# V1.net
KiCad netlist of a schematic drawn in EAGLE
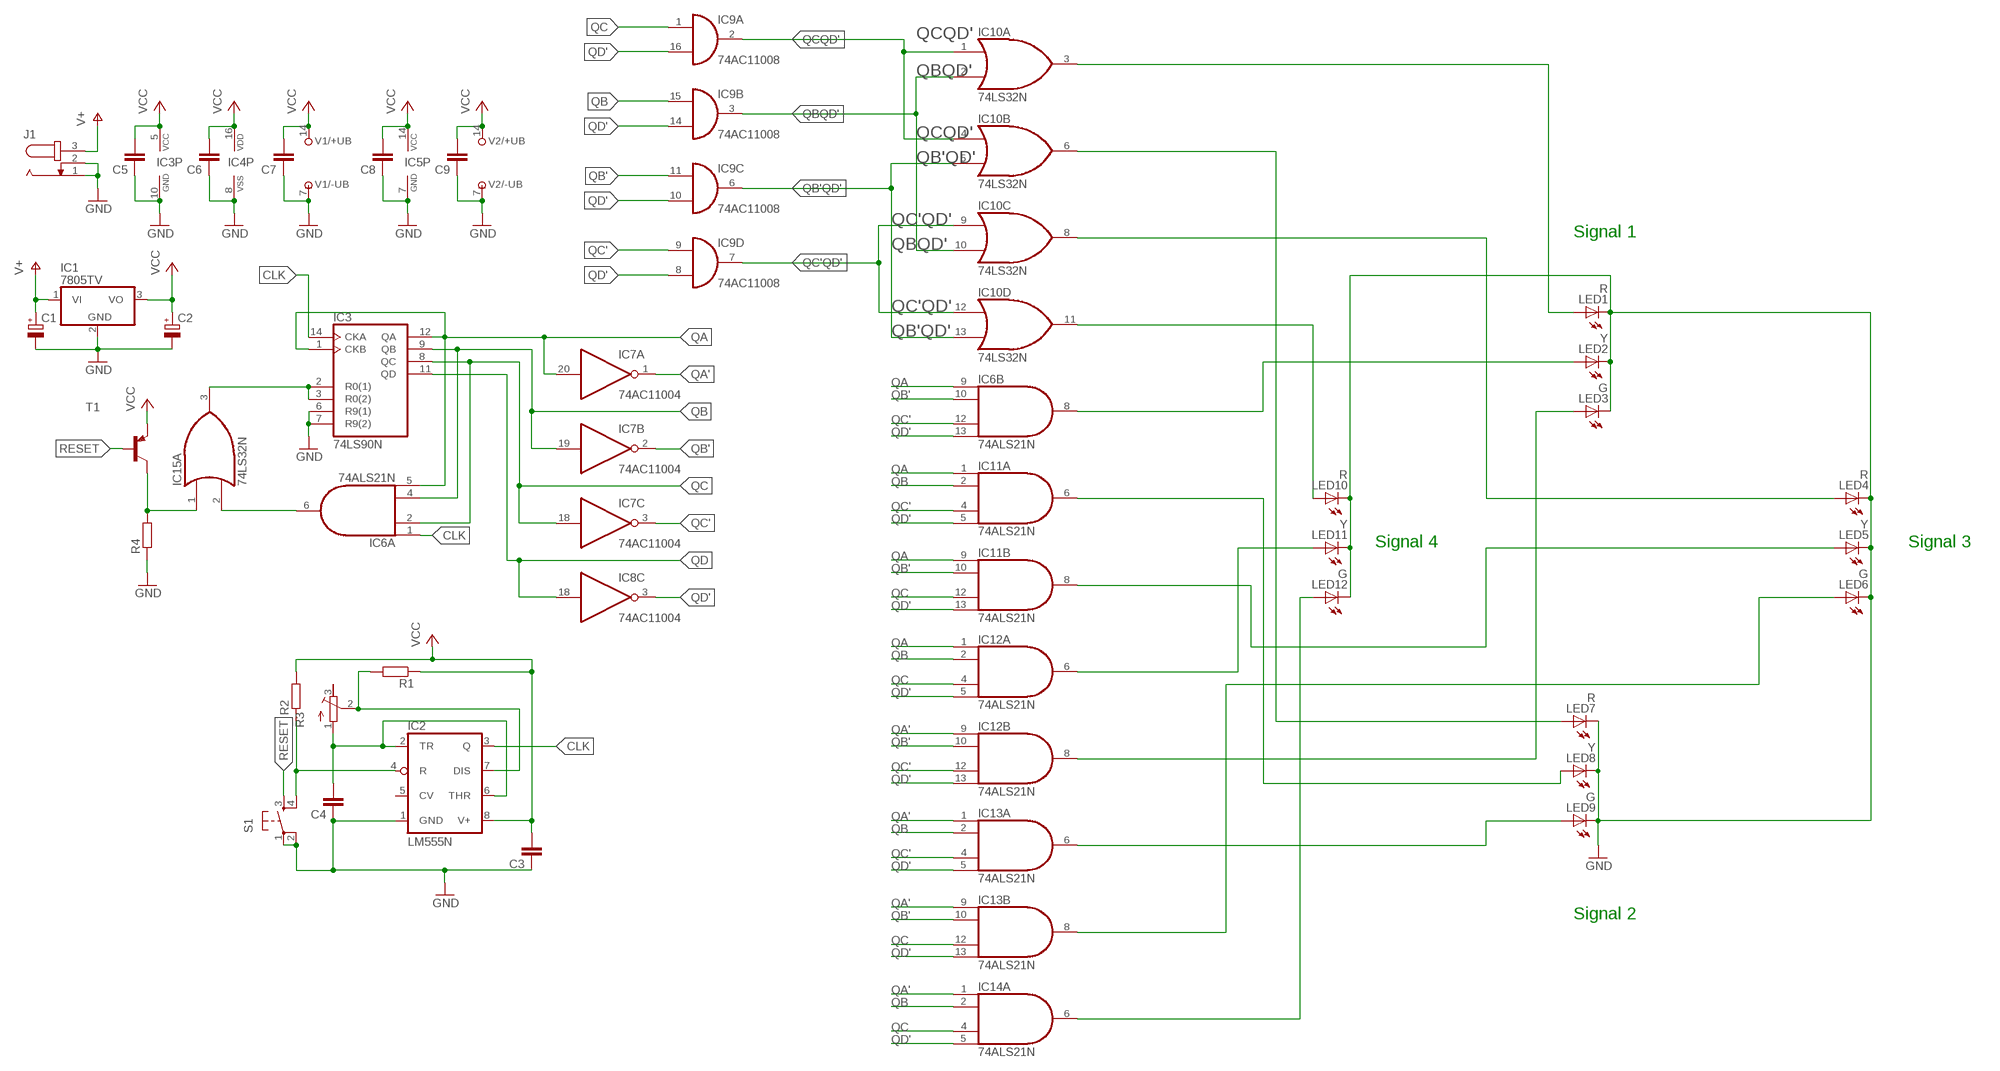
[diagram p0: schematic, sheet 1]

(export (version "E")
  (design (tool "Eeschema 10.0.6"))
  (components
    (comp (ref "C1")
      (value "CPOL-EUE3.5-8")
      (footprint "eagle-import:E3,5-8")
      (libsource (lib "eagle-import") (part "CPOL-EUE3.5-8"))
    )
    (comp (ref "C2")
      (value "CPOL-EUE3.5-8")
      (footprint "eagle-import:E3,5-8")
      (libsource (lib "eagle-import") (part "CPOL-EUE3.5-8"))
    )
    (comp (ref "C3")
      (value "C-EU050-035X075")
      (footprint "eagle-import:C050-035X075")
      (libsource (lib "eagle-import") (part "C-EU050-035X075"))
    )
    (comp (ref "C4")
      (value "C-EU050-035X075")
      (footprint "eagle-import:C050-035X075")
      (libsource (lib "eagle-import") (part "C-EU050-035X075"))
    )
    (comp (ref "C5")
      (value "C-EU050-035X075")
      (footprint "eagle-import:C050-035X075")
      (libsource (lib "eagle-import") (part "C-EU050-035X075"))
    )
    (comp (ref "C6")
      (value "C-EU050-035X075")
      (footprint "eagle-import:C050-035X075")
      (libsource (lib "eagle-import") (part "C-EU050-035X075"))
    )
    (comp (ref "C7")
      (value "C-EU050-035X075")
      (footprint "eagle-import:C050-035X075")
      (libsource (lib "eagle-import") (part "C-EU050-035X075"))
    )
    (comp (ref "C8")
      (value "C-EU050-035X075")
      (footprint "eagle-import:C050-035X075")
      (libsource (lib "eagle-import") (part "C-EU050-035X075"))
    )
    (comp (ref "C9")
      (value "C-EU050-035X075")
      (footprint "eagle-import:C050-035X075")
      (libsource (lib "eagle-import") (part "C-EU050-035X075"))
    )
    (comp (ref "IC1")
      (value "7805TV")
      (footprint "eagle-import:TO220V")
      (libsource (lib "eagle-import") (part "78TV05"))
    )
    (comp (ref "IC2")
      (value "LM555N")
      (footprint "eagle-import:DIL08")
      (libsource (lib "eagle-import") (part "555NLM"))
    )
    (comp (ref "IC3")
      (value "74LS90N")
      (footprint "eagle-import:DIL14")
      (libsource (lib "eagle-import") (part "7490NLS"))
    )
    (comp (ref "IC4")
      (value "4028N")
      (footprint "eagle-import:DIL16")
      (libsource (lib "eagle-import") (part "4028N"))
    )
    (comp (ref "IC5")
      (value "74AC04N")
      (footprint "eagle-import:DIL14")
      (libsource (lib "eagle-import") (part "7404NAC"))
    )
    (comp (ref "IC6")
      (value "74ALS21N")
      (footprint "eagle-import:DIL14")
      (libsource (lib "eagle-import") (part "7421NALS"))
    )
    (comp (ref "IC7")
      (value "74AC11004")
      (footprint "eagle-import:DIL20")
      (libsource (lib "eagle-import") (part "74AC11004"))
    )
    (comp (ref "IC8")
      (value "74AC11004")
      (footprint "eagle-import:DIL20")
      (libsource (lib "eagle-import") (part "74AC11004"))
    )
    (comp (ref "IC9")
      (value "74AC11008")
      (footprint "eagle-import:DIL16")
      (libsource (lib "eagle-import") (part "74AC11008"))
    )
    (comp (ref "IC10")
      (value "74LS32N")
      (footprint "eagle-import:DIL14")
      (libsource (lib "eagle-import") (part "7432NLS"))
    )
    (comp (ref "IC11")
      (value "74ALS21N")
      (footprint "eagle-import:DIL14")
      (libsource (lib "eagle-import") (part "7421NALS"))
    )
    (comp (ref "IC12")
      (value "74ALS21N")
      (footprint "eagle-import:DIL14")
      (libsource (lib "eagle-import") (part "7421NALS"))
    )
    (comp (ref "IC13")
      (value "74ALS21N")
      (footprint "eagle-import:DIL14")
      (libsource (lib "eagle-import") (part "7421NALS"))
    )
    (comp (ref "IC14")
      (value "74ALS21N")
      (footprint "eagle-import:DIL14")
      (libsource (lib "eagle-import") (part "7421NALS"))
    )
    (comp (ref "IC15")
      (value "74LS32N")
      (footprint "eagle-import:DIL14")
      (libsource (lib "eagle-import") (part "7432NLS"))
    )
    (comp (ref "J1")
      (value "JACK-PLUG0")
      (footprint "eagle-import:SPC4077")
      (libsource (lib "eagle-import") (part "JACK-PLUG0"))
    )
    (comp (ref "LED1")
      (value "R")
      (footprint "eagle-import:LED5MM")
      (libsource (lib "eagle-import") (part "LED5MM"))
    )
    (comp (ref "LED2")
      (value "Y")
      (footprint "eagle-import:LED5MM")
      (libsource (lib "eagle-import") (part "LED5MM"))
    )
    (comp (ref "LED3")
      (value "G")
      (footprint "eagle-import:LED5MM")
      (libsource (lib "eagle-import") (part "LED5MM"))
    )
    (comp (ref "LED4")
      (value "R")
      (footprint "eagle-import:LED5MM")
      (libsource (lib "eagle-import") (part "LED5MM"))
    )
    (comp (ref "LED5")
      (value "Y")
      (footprint "eagle-import:LED5MM")
      (libsource (lib "eagle-import") (part "LED5MM"))
    )
    (comp (ref "LED6")
      (value "G")
      (footprint "eagle-import:LED5MM")
      (libsource (lib "eagle-import") (part "LED5MM"))
    )
    (comp (ref "LED7")
      (value "R")
      (footprint "eagle-import:LED5MM")
      (libsource (lib "eagle-import") (part "LED5MM"))
    )
    (comp (ref "LED8")
      (value "Y")
      (footprint "eagle-import:LED5MM")
      (libsource (lib "eagle-import") (part "LED5MM"))
    )
    (comp (ref "LED9")
      (value "G")
      (footprint "eagle-import:LED5MM")
      (libsource (lib "eagle-import") (part "LED5MM"))
    )
    (comp (ref "LED10")
      (value "R")
      (footprint "eagle-import:LED5MM")
      (libsource (lib "eagle-import") (part "LED5MM"))
    )
    (comp (ref "LED11")
      (value "Y")
      (footprint "eagle-import:LED5MM")
      (libsource (lib "eagle-import") (part "LED5MM"))
    )
    (comp (ref "LED12")
      (value "G")
      (footprint "eagle-import:LED5MM")
      (libsource (lib "eagle-import") (part "LED5MM"))
    )
    (comp (ref "R1")
      (value "R-EU_0207/7")
      (footprint "eagle-import:0207_7")
      (libsource (lib "eagle-import") (part "R-EU_0207/7"))
    )
    (comp (ref "R2")
      (value "R-EU_0207/7")
      (footprint "eagle-import:0207_7")
      (libsource (lib "eagle-import") (part "R-EU_0207/7"))
    )
    (comp (ref "R3")
      (value "R-TRIMM3296W")
      (footprint "eagle-import:RTRIM3296W")
      (libsource (lib "eagle-import") (part "R-TRIMM3296W"))
    )
    (comp (ref "R4")
      (value "R-EU_0207/7")
      (footprint "eagle-import:0207_7")
      (libsource (lib "eagle-import") (part "R-EU_0207/7"))
    )
    (comp (ref "S1")
      (value "TAC_SWITCHPTH")
      (footprint "eagle-import:TACTILE-PTH")
      (libsource (lib "eagle-import") (part "TAC_SWITCHPTH"))
    )
    (comp (ref "T1")
      (value "-PNP-TO92/")
      (footprint "eagle-import:TO92_")
      (libsource (lib "eagle-import") (part "-PNP-TO92/"))
    )
    (comp (ref "V1")
      (value "7432N")
      (footprint "eagle-import:DIL14")
      (libsource (lib "eagle-import") (part "7432N"))
    )
    (comp (ref "V2")
      (value "7432N")
      (footprint "eagle-import:DIL14")
      (libsource (lib "eagle-import") (part "7432N"))
    )
  )
  (nets
    (net (code "1") (name "CLK") (class "Default")
      (node (ref "IC2") (pin "3") (pinfunction "Q_3") (pintype "output"))
      (node (ref "IC3") (pin "14") (pinfunction "CKA_14") (pintype "input"))
      (node (ref "IC6") (pin "1") (pinfunction "I0_1") (pintype "input"))
    )
    (net (code "2") (name "GND") (class "Default")
      (node (ref "C1") (pin "-") (pinfunction "-_-") (pintype "passive"))
      (node (ref "C2") (pin "-") (pinfunction "-_-") (pintype "passive"))
      (node (ref "C3") (pin "1") (pinfunction "1_1") (pintype "passive"))
      (node (ref "C4") (pin "1") (pinfunction "1_1") (pintype "passive"))
      (node (ref "C5") (pin "1") (pinfunction "1_1") (pintype "passive"))
      (node (ref "C6") (pin "1") (pinfunction "1_1") (pintype "passive"))
      (node (ref "C7") (pin "1") (pinfunction "1_1") (pintype "passive"))
      (node (ref "C8") (pin "1") (pinfunction "1_1") (pintype "passive"))
      (node (ref "C9") (pin "1") (pinfunction "1_1") (pintype "passive"))
      (node (ref "IC1") (pin "2") (pinfunction "GND_2") (pintype "passive"))
      (node (ref "IC2") (pin "1") (pinfunction "GND_1") (pintype "power_in"))
      (node (ref "IC3") (pin "10") (pinfunction "GND_10") (pintype "power_in"))
      (node (ref "IC3") (pin "6") (pinfunction "R9(1)_6") (pintype "input"))
      (node (ref "IC3") (pin "7") (pinfunction "R9(2)_7") (pintype "input"))
      (node (ref "IC4") (pin "8") (pinfunction "VSS_8") (pintype "power_in"))
      (node (ref "IC5") (pin "7") (pinfunction "GND_7") (pintype "power_in"))
      (node (ref "J1") (pin "1") (pinfunction "1_1") (pintype "passive"))
      (node (ref "J1") (pin "2") (pinfunction "2_2") (pintype "passive"))
      (node (ref "LED1") (pin "K") (pinfunction "C_K") (pintype "passive"))
      (node (ref "LED10") (pin "K") (pinfunction "C_K") (pintype "passive"))
      (node (ref "LED11") (pin "K") (pinfunction "C_K") (pintype "passive"))
      (node (ref "LED12") (pin "K") (pinfunction "C_K") (pintype "passive"))
      (node (ref "LED2") (pin "K") (pinfunction "C_K") (pintype "passive"))
      (node (ref "LED3") (pin "K") (pinfunction "C_K") (pintype "passive"))
      (node (ref "LED4") (pin "K") (pinfunction "C_K") (pintype "passive"))
      (node (ref "LED5") (pin "K") (pinfunction "C_K") (pintype "passive"))
      (node (ref "LED6") (pin "K") (pinfunction "C_K") (pintype "passive"))
      (node (ref "LED7") (pin "K") (pinfunction "C_K") (pintype "passive"))
      (node (ref "LED8") (pin "K") (pinfunction "C_K") (pintype "passive"))
      (node (ref "LED9") (pin "K") (pinfunction "C_K") (pintype "passive"))
      (node (ref "R4") (pin "1") (pinfunction "1_1") (pintype "passive"))
      (node (ref "S1") (pin "1") (pinfunction "1_1") (pintype "passive"))
      (node (ref "S1") (pin "2") (pinfunction "2_2") (pintype "passive"))
      (node (ref "V1") (pin "7") (pinfunction "-UB_7") (pintype "power_in"))
      (node (ref "V2") (pin "7") (pinfunction "-UB_7") (pintype "power_in"))
    )
    (net (code "3") (name "Net-(IC2-DIS)") (class "Default")
      (node (ref "IC2") (pin "7") (pinfunction "DIS_7") (pintype "input"))
      (node (ref "R1") (pin "2") (pinfunction "2_2") (pintype "passive"))
      (node (ref "R3") (pin "2") (pinfunction "S_2") (pintype "passive"))
    )
    (net (code "4") (name "Net-(IC2-R)") (class "Default")
      (node (ref "IC2") (pin "4") (pinfunction "R_4") (pintype "input"))
      (node (ref "R2") (pin "1") (pinfunction "1_1") (pintype "passive"))
      (node (ref "S1") (pin "4") (pinfunction "4_4") (pintype "passive"))
    )
    (net (code "5") (name "Net-(IC2-THR)") (class "Default")
      (node (ref "C4") (pin "2") (pinfunction "2_2") (pintype "passive"))
      (node (ref "IC2") (pin "2") (pinfunction "TR_2") (pintype "input"))
      (node (ref "IC2") (pin "6") (pinfunction "THR_6") (pintype "input"))
      (node (ref "R3") (pin "1") (pinfunction "A_1") (pintype "passive"))
    )
    (net (code "6") (name "Net-(IC6B-O)") (class "Default")
      (node (ref "IC6") (pin "8") (pinfunction "O_8") (pintype "output"))
      (node (ref "LED2") (pin "A") (pinfunction "A_A") (pintype "passive"))
    )
    (net (code "7") (name "Net-(IC10A-O)") (class "Default")
      (node (ref "IC10") (pin "3") (pinfunction "O_3") (pintype "output"))
      (node (ref "LED1") (pin "A") (pinfunction "A_A") (pintype "passive"))
    )
    (net (code "8") (name "Net-(IC10B-O)") (class "Default")
      (node (ref "IC10") (pin "6") (pinfunction "O_6") (pintype "output"))
      (node (ref "LED7") (pin "A") (pinfunction "A_A") (pintype "passive"))
    )
    (net (code "9") (name "Net-(IC10C-O)") (class "Default")
      (node (ref "IC10") (pin "8") (pinfunction "O_8") (pintype "output"))
      (node (ref "LED4") (pin "A") (pinfunction "A_A") (pintype "passive"))
    )
    (net (code "10") (name "Net-(IC10D-O)") (class "Default")
      (node (ref "IC10") (pin "11") (pinfunction "O_11") (pintype "output"))
      (node (ref "LED10") (pin "A") (pinfunction "A_A") (pintype "passive"))
    )
    (net (code "11") (name "Net-(IC11A-O)") (class "Default")
      (node (ref "IC11") (pin "6") (pinfunction "O_6") (pintype "output"))
      (node (ref "LED8") (pin "A") (pinfunction "A_A") (pintype "passive"))
    )
    (net (code "12") (name "Net-(IC11B-O)") (class "Default")
      (node (ref "IC11") (pin "8") (pinfunction "O_8") (pintype "output"))
      (node (ref "LED5") (pin "A") (pinfunction "A_A") (pintype "passive"))
    )
    (net (code "13") (name "Net-(IC12A-O)") (class "Default")
      (node (ref "IC12") (pin "6") (pinfunction "O_6") (pintype "output"))
      (node (ref "LED11") (pin "A") (pinfunction "A_A") (pintype "passive"))
    )
    (net (code "14") (name "Net-(IC12B-O)") (class "Default")
      (node (ref "IC12") (pin "8") (pinfunction "O_8") (pintype "output"))
      (node (ref "LED3") (pin "A") (pinfunction "A_A") (pintype "passive"))
    )
    (net (code "15") (name "Net-(IC13A-O)") (class "Default")
      (node (ref "IC13") (pin "6") (pinfunction "O_6") (pintype "output"))
      (node (ref "LED9") (pin "A") (pinfunction "A_A") (pintype "passive"))
    )
    (net (code "16") (name "Net-(IC13B-O)") (class "Default")
      (node (ref "IC13") (pin "8") (pinfunction "O_8") (pintype "output"))
      (node (ref "LED6") (pin "A") (pinfunction "A_A") (pintype "passive"))
    )
    (net (code "17") (name "Net-(IC14A-O)") (class "Default")
      (node (ref "IC14") (pin "6") (pinfunction "O_6") (pintype "output"))
      (node (ref "LED12") (pin "A") (pinfunction "A_A") (pintype "passive"))
    )
    (net (code "18") (name "Net-(IC15A-I0)") (class "Default")
      (node (ref "IC15") (pin "1") (pinfunction "I0_1") (pintype "input"))
      (node (ref "R4") (pin "2") (pinfunction "2_2") (pintype "passive"))
      (node (ref "T1") (pin "3") (pinfunction "C_3") (pintype "passive"))
    )
    (net (code "19") (name "Net-(IC15A-I1)") (class "Default")
      (node (ref "IC15") (pin "2") (pinfunction "I1_2") (pintype "input"))
      (node (ref "IC6") (pin "6") (pinfunction "O_6") (pintype "output"))
    )
    (net (code "20") (name "Net-(IC15A-O)") (class "Default")
      (node (ref "IC15") (pin "3") (pinfunction "O_3") (pintype "output"))
      (node (ref "IC3") (pin "2") (pinfunction "R0(1)_2") (pintype "input"))
      (node (ref "IC3") (pin "3") (pinfunction "R0(2)_3") (pintype "input"))
    )
    (net (code "21") (name "QA") (class "Default")
      (node (ref "IC11") (pin "1") (pinfunction "I0_1") (pintype "input"))
      (node (ref "IC11") (pin "9") (pinfunction "I0_9") (pintype "input"))
      (node (ref "IC12") (pin "1") (pinfunction "I0_1") (pintype "input"))
      (node (ref "IC3") (pin "1") (pinfunction "CKB_1") (pintype "input"))
      (node (ref "IC3") (pin "12") (pinfunction "QA_12") (pintype "output"))
      (node (ref "IC6") (pin "5") (pinfunction "I3_5") (pintype "input"))
      (node (ref "IC6") (pin "9") (pinfunction "I0_9") (pintype "input"))
      (node (ref "IC7") (pin "20") (pinfunction "I_20") (pintype "input"))
    )
    (net (code "22") (name "QA'") (class "Default")
      (node (ref "IC12") (pin "9") (pinfunction "I0_9") (pintype "input"))
      (node (ref "IC13") (pin "1") (pinfunction "I0_1") (pintype "input"))
      (node (ref "IC13") (pin "9") (pinfunction "I0_9") (pintype "input"))
      (node (ref "IC14") (pin "1") (pinfunction "I0_1") (pintype "input"))
      (node (ref "IC7") (pin "1") (pinfunction "O_1") (pintype "output"))
    )
    (net (code "23") (name "QB") (class "Default")
      (node (ref "IC11") (pin "2") (pinfunction "I1_2") (pintype "input"))
      (node (ref "IC12") (pin "2") (pinfunction "I1_2") (pintype "input"))
      (node (ref "IC13") (pin "2") (pinfunction "I1_2") (pintype "input"))
      (node (ref "IC14") (pin "2") (pinfunction "I1_2") (pintype "input"))
      (node (ref "IC3") (pin "9") (pinfunction "QB_9") (pintype "output"))
      (node (ref "IC6") (pin "4") (pinfunction "I2_4") (pintype "input"))
      (node (ref "IC7") (pin "19") (pinfunction "I_19") (pintype "input"))
      (node (ref "IC9") (pin "15") (pinfunction "I0_15") (pintype "input"))
    )
    (net (code "24") (name "QB'") (class "Default")
      (node (ref "IC11") (pin "10") (pinfunction "I1_10") (pintype "input"))
      (node (ref "IC12") (pin "10") (pinfunction "I1_10") (pintype "input"))
      (node (ref "IC13") (pin "10") (pinfunction "I1_10") (pintype "input"))
      (node (ref "IC6") (pin "10") (pinfunction "I1_10") (pintype "input"))
      (node (ref "IC7") (pin "2") (pinfunction "O_2") (pintype "output"))
      (node (ref "IC9") (pin "11") (pinfunction "I0_11") (pintype "input"))
    )
    (net (code "25") (name "QB'QD'") (class "Default")
      (node (ref "IC10") (pin "13") (pinfunction "I1_13") (pintype "input"))
      (node (ref "IC10") (pin "5") (pinfunction "I1_5") (pintype "input"))
      (node (ref "IC9") (pin "6") (pinfunction "O_6") (pintype "output"))
    )
    (net (code "26") (name "QBQD'") (class "Default")
      (node (ref "IC10") (pin "10") (pinfunction "I1_10") (pintype "input"))
      (node (ref "IC10") (pin "2") (pinfunction "I1_2") (pintype "input"))
      (node (ref "IC9") (pin "3") (pinfunction "O_3") (pintype "output"))
    )
    (net (code "27") (name "QC") (class "Default")
      (node (ref "IC11") (pin "12") (pinfunction "I2_12") (pintype "input"))
      (node (ref "IC12") (pin "4") (pinfunction "I2_4") (pintype "input"))
      (node (ref "IC13") (pin "12") (pinfunction "I2_12") (pintype "input"))
      (node (ref "IC14") (pin "4") (pinfunction "I2_4") (pintype "input"))
      (node (ref "IC3") (pin "8") (pinfunction "QC_8") (pintype "output"))
      (node (ref "IC6") (pin "2") (pinfunction "I1_2") (pintype "input"))
      (node (ref "IC7") (pin "18") (pinfunction "I_18") (pintype "input"))
      (node (ref "IC9") (pin "1") (pinfunction "I0_1") (pintype "input"))
    )
    (net (code "28") (name "QC'") (class "Default")
      (node (ref "IC11") (pin "4") (pinfunction "I2_4") (pintype "input"))
      (node (ref "IC12") (pin "12") (pinfunction "I2_12") (pintype "input"))
      (node (ref "IC13") (pin "4") (pinfunction "I2_4") (pintype "input"))
      (node (ref "IC6") (pin "12") (pinfunction "I2_12") (pintype "input"))
      (node (ref "IC7") (pin "3") (pinfunction "O_3") (pintype "output"))
      (node (ref "IC9") (pin "9") (pinfunction "I0_9") (pintype "input"))
    )
    (net (code "29") (name "QC'QD'") (class "Default")
      (node (ref "IC10") (pin "12") (pinfunction "I0_12") (pintype "input"))
      (node (ref "IC10") (pin "9") (pinfunction "I0_9") (pintype "input"))
      (node (ref "IC9") (pin "7") (pinfunction "O_7") (pintype "output"))
    )
    (net (code "30") (name "QCQD'") (class "Default")
      (node (ref "IC10") (pin "1") (pinfunction "I0_1") (pintype "input"))
      (node (ref "IC10") (pin "4") (pinfunction "I0_4") (pintype "input"))
      (node (ref "IC9") (pin "2") (pinfunction "O_2") (pintype "output"))
    )
    (net (code "31") (name "QD") (class "Default")
      (node (ref "IC3") (pin "11") (pinfunction "QD_11") (pintype "output"))
      (node (ref "IC8") (pin "18") (pinfunction "I_18") (pintype "input"))
    )
    (net (code "32") (name "QD'") (class "Default")
      (node (ref "IC11") (pin "13") (pinfunction "I3_13") (pintype "input"))
      (node (ref "IC11") (pin "5") (pinfunction "I3_5") (pintype "input"))
      (node (ref "IC12") (pin "13") (pinfunction "I3_13") (pintype "input"))
      (node (ref "IC12") (pin "5") (pinfunction "I3_5") (pintype "input"))
      (node (ref "IC13") (pin "13") (pinfunction "I3_13") (pintype "input"))
      (node (ref "IC13") (pin "5") (pinfunction "I3_5") (pintype "input"))
      (node (ref "IC14") (pin "5") (pinfunction "I3_5") (pintype "input"))
      (node (ref "IC6") (pin "13") (pinfunction "I3_13") (pintype "input"))
      (node (ref "IC8") (pin "3") (pinfunction "O_3") (pintype "output"))
      (node (ref "IC9") (pin "10") (pinfunction "I1_10") (pintype "input"))
      (node (ref "IC9") (pin "14") (pinfunction "I1_14") (pintype "input"))
      (node (ref "IC9") (pin "16") (pinfunction "I1_16") (pintype "input"))
      (node (ref "IC9") (pin "8") (pinfunction "I1_8") (pintype "input"))
    )
    (net (code "33") (name "RESET") (class "Default")
      (node (ref "S1") (pin "3") (pinfunction "3_3") (pintype "passive"))
      (node (ref "T1") (pin "2") (pinfunction "B_2") (pintype "passive"))
    )
    (net (code "34") (name "V+") (class "Default")
      (node (ref "C1") (pin "+") (pinfunction "+_+") (pintype "passive"))
      (node (ref "IC1") (pin "1") (pinfunction "VI_1") (pintype "input"))
      (node (ref "J1") (pin "3") (pinfunction "3_3") (pintype "passive"))
    )
    (net (code "35") (name "VCC") (class "Default")
      (node (ref "C2") (pin "+") (pinfunction "+_+") (pintype "passive"))
      (node (ref "C3") (pin "2") (pinfunction "2_2") (pintype "passive"))
      (node (ref "C5") (pin "2") (pinfunction "2_2") (pintype "passive"))
      (node (ref "C6") (pin "2") (pinfunction "2_2") (pintype "passive"))
      (node (ref "C7") (pin "2") (pinfunction "2_2") (pintype "passive"))
      (node (ref "C8") (pin "2") (pinfunction "2_2") (pintype "passive"))
      (node (ref "C9") (pin "2") (pinfunction "2_2") (pintype "passive"))
      (node (ref "IC1") (pin "3") (pinfunction "VO_3") (pintype "passive"))
      (node (ref "IC2") (pin "8") (pinfunction "V+_8") (pintype "power_in"))
      (node (ref "IC3") (pin "5") (pinfunction "VCC_5") (pintype "power_in"))
      (node (ref "IC4") (pin "16") (pinfunction "VDD_16") (pintype "power_in"))
      (node (ref "IC5") (pin "14") (pinfunction "VCC_14") (pintype "power_in"))
      (node (ref "R1") (pin "1") (pinfunction "1_1") (pintype "passive"))
      (node (ref "R2") (pin "2") (pinfunction "2_2") (pintype "passive"))
      (node (ref "T1") (pin "1") (pinfunction "E_1") (pintype "passive"))
      (node (ref "V1") (pin "14") (pinfunction "+UB_14") (pintype "power_in"))
      (node (ref "V2") (pin "14") (pinfunction "+UB_14") (pintype "power_in"))
    )
    (net (code "36") (name "unconnected-(IC2-CV-Pad5)") (class "Default")
      (node (ref "IC2") (pin "5") (pinfunction "CV_5") (pintype "input"))
    )
    (net (code "37") (name "unconnected-(R3-E-Pad3)") (class "Default")
      (node (ref "R3") (pin "3") (pinfunction "E_3") (pintype "passive"))
    )
  )
)
